# doan1.net
KiCad netlist of a schematic drawn in Altium Designer
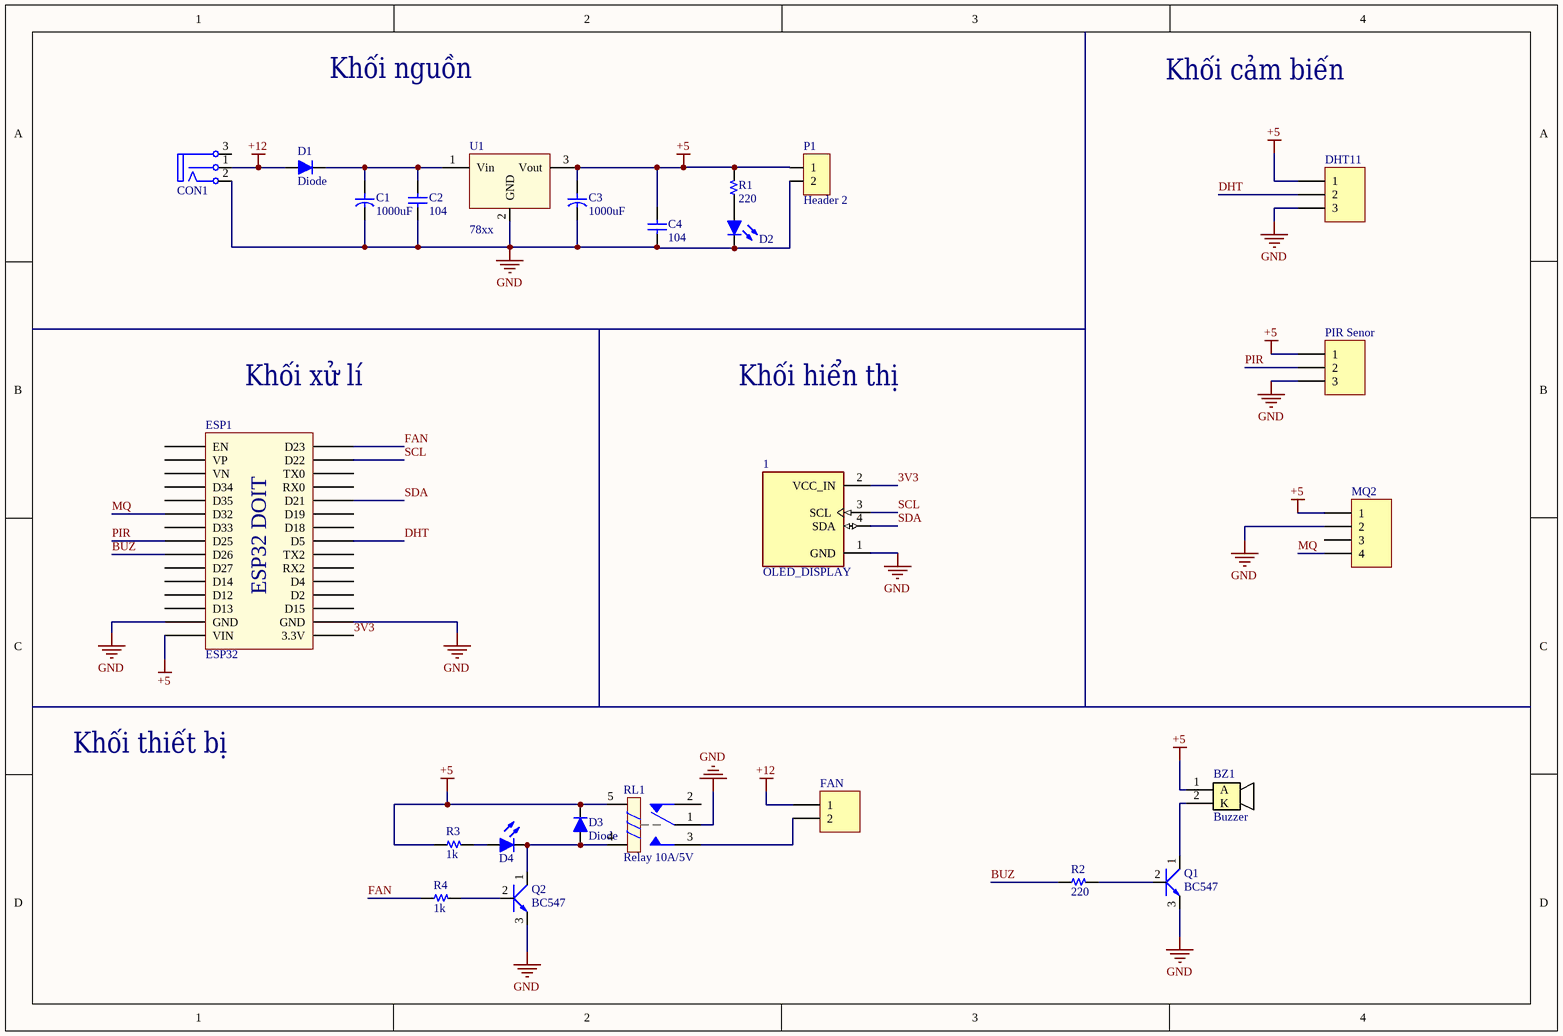
[diagram p0: doan1.SchDoc]

(export (version "E")
  (design (tool "Eeschema 10.0.6"))
  (components
    (comp (ref "1")
      (value "OLED_DISPLAY")
      (footprint "MODULE_DM-OLED096-636")
      (description "0.96â€ 128 X 64 MONOCHROME GRAPHIC OLED DISPLAY MODULE - I2C")
      (fields (field (name "MF") "Display Module") (field (name "MP") "DM-OLED096-636"))
      (libsource (lib "DM-OLED096-636") (part "DM-OLED096-636"))
    )
    (comp (ref "BZ1") (value "Buzzer") (footprint "BUZZER") (libsource (lib "chipfc_libs") (part "Buzzer")))
    (comp (ref "C1")
      (value "1000uF")
      (footprint "CYL/D.400/LS.200")
      (description "Capacitor pol")
      (libsource (lib "chipfc_libs") (part "Capacitor"))
    )
    (comp (ref "C2")
      (value "104")
      (footprint "CAP Ceramic/W300")
      (description "Capacitor non-pol")
      (libsource (lib "chipfc_libs") (part "Capacitor NP"))
    )
    (comp (ref "C3")
      (value "1000uF")
      (footprint "CYL/D.400/LS.200")
      (description "Capacitor pol")
      (libsource (lib "chipfc_libs") (part "Capacitor"))
    )
    (comp (ref "C4")
      (value "104")
      (footprint "CAP Ceramic/W300")
      (description "Capacitor non-pol")
      (libsource (lib "chipfc_libs") (part "Capacitor NP"))
    )
    (comp (ref "CON1")
      (value "CON DC PWR")
      (footprint "CONN/DC/PWR/5.0MM")
      (description "DC input connector")
      (libsource (lib "connectors") (part "CON DC PWR"))
    )
    (comp (ref "D1")
      (value "Diode")
      (footprint "DO-41")
      (description "Default Diode")
      (libsource (lib "chipfc_libs") (part "Diode"))
    )
    (comp (ref "D2")
      (value "Led")
      (footprint "LED 3MM - red")
      (description "Typical LED")
      (libsource (lib "led") (part "Led"))
    )
    (comp (ref "D3")
      (value "Diode")
      (footprint "DO-41")
      (description "Default Diode")
      (libsource (lib "chipfc_libs") (part "Diode"))
    )
    (comp (ref "D4")
      (value "Led")
      (footprint "LED 3MM - red")
      (description "Typical LED")
      (libsource (lib "led") (part "Led"))
    )
    (comp (ref "DHT11")
      (value "Header 3")
      (footprint "MY_FE03")
      (description "Header, 3-Pin")
      (fields (field (name "ASID PART NUMBER") "Header 3-AS"))
      (libsource (lib "003 Mylib-Rev-4") (part "Header 3"))
    )
    (comp (ref "ESP1")
      (value "ESP32")
      (footprint "ESP32 WROOM 32 KIT")
      (libsource (lib "Altium_Lib_by_KhueNguyenCreator") (part "ESP32 WROOM 32 KIT"))
    )
    (comp (ref "FAN")
      (value "Header 2")
      (footprint "My_CN2")
      (description "Header, 2-Pin")
      (fields (field (name "ASID PART NUMBER") "Header 2-AS"))
      (libsource (lib "003 Mylib-Rev-4") (part "Header 2"))
    )
    (comp (ref "MQ2")
      (value "Header 4")
      (footprint "MY_FE04")
      (description "Header, 4-Pin")
      (fields (field (name "ASID PART NUMBER") "Header 4-AS"))
      (libsource (lib "003 Mylib-Rev-4") (part "Header 4"))
    )
    (comp (ref "P1")
      (value "Header 2")
      (footprint "HDR/Header/2")
      (description "Header, 2-Pin")
      (libsource (lib "connectors") (part "Header 2"))
    )
    (comp (ref "PIR Senor")
      (value "Header 3")
      (footprint "MY_FE03W")
      (description "Header, 3-Pin")
      (fields (field (name "ASID PART NUMBER") "Header 3-AS"))
      (libsource (lib "003 Mylib-Rev-4") (part "Header 3"))
    )
    (comp (ref "Q1")
      (value "BC547")
      (footprint "QTO-92")
      (description "NPN 600mW, ECB")
      (libsource (lib "syhaunguyen") (part "C1815"))
    )
    (comp (ref "Q2")
      (value "BC547")
      (footprint "QTO-92")
      (description "NPN 600mW, ECB")
      (libsource (lib "syhaunguyen") (part "C1815"))
    )
    (comp (ref "R1")
      (value "220")
      (footprint "R 1/4W/300")
      (description "Resistor")
      (libsource (lib "chipfc_libs") (part "Resistor"))
    )
    (comp (ref "R2")
      (value "220")
      (footprint "R 1/4W/300")
      (description "Resistor")
      (libsource (lib "chipfc_libs") (part "Resistor"))
    )
    (comp (ref "R3")
      (value "1k")
      (footprint "R 1/4W/300")
      (description "Resistor")
      (libsource (lib "chipfc_libs") (part "Resistor"))
    )
    (comp (ref "R4")
      (value "1k")
      (footprint "R 1/4W/300")
      (description "Resistor")
      (libsource (lib "chipfc_libs") (part "Resistor"))
    )
    (comp (ref "RL1")
      (value "Relay 10A/5V")
      (footprint "RL_SPDT_10A")
      (description "Relay SPDT,10A - 12VDC 5 Pin")
      (libsource (lib "syhaunguyen") (part "Relay 1"))
    )
    (comp (ref "U1")
      (value "78xx")
      (footprint "TO-220")
      (description "LDO Fixed Voltage regulator")
      (libsource (lib "chipfc_libs") (part "78xx"))
    )
  )
  (nets
    (net (code "1") (name "+5") (class "Default")
      (node (ref "BZ1") (pin "1") (pinfunction "A_1") (pintype "passive"))
      (node (ref "C3") (pin "1") (pinfunction "1_1") (pintype "passive"))
      (node (ref "C4") (pin "1") (pinfunction "1_1") (pintype "passive"))
      (node (ref "D3") (pin "2") (pinfunction "K_2") (pintype "passive"))
      (node (ref "DHT11") (pin "1") (pinfunction "1_1") (pintype "passive"))
      (node (ref "ESP1") (pin "15") (pinfunction "VIN_15") (pintype "passive"))
      (node (ref "MQ2") (pin "1") (pinfunction "1_1") (pintype "passive"))
      (node (ref "P1") (pin "1") (pinfunction "1_1") (pintype "passive"))
      (node (ref "PIR Senor") (pin "1") (pinfunction "1_1") (pintype "passive"))
      (node (ref "R1") (pin "2") (pinfunction "2_2") (pintype "passive"))
      (node (ref "R3") (pin "1") (pinfunction "1_1") (pintype "passive"))
      (node (ref "RL1") (pin "5") (pinfunction "5_5") (pintype "passive"))
      (node (ref "U1") (pin "3") (pinfunction "Vout_3") (pintype "passive"))
    )
    (net (code "2") (name "+12") (class "Default")
      (node (ref "CON1") (pin "1") (pinfunction "S_1") (pintype "power_in"))
      (node (ref "D1") (pin "1") (pinfunction "A_1") (pintype "passive"))
      (node (ref "FAN") (pin "1") (pinfunction "1_1") (pintype "passive"))
    )
    (net (code "3") (name "/3V3") (class "Default")
      (node (ref "1") (pin "2") (pinfunction "VCC_IN_2") (pintype "power_in"))
      (node (ref "ESP1") (pin "16") (pinfunction "3.3V_16") (pintype "passive"))
    )
    (net (code "4") (name "/BUZ") (class "Default")
      (node (ref "ESP1") (pin "9") (pinfunction "D26_9") (pintype "passive"))
      (node (ref "R2") (pin "1") (pinfunction "1_1") (pintype "passive"))
    )
    (net (code "5") (name "/DHT") (class "Default")
      (node (ref "DHT11") (pin "2") (pinfunction "2_2") (pintype "passive"))
      (node (ref "ESP1") (pin "23") (pinfunction "D5_23") (pintype "passive"))
    )
    (net (code "6") (name "/FAN") (class "Default")
      (node (ref "ESP1") (pin "30") (pinfunction "D23_30") (pintype "passive"))
      (node (ref "R4") (pin "1") (pinfunction "1_1") (pintype "passive"))
    )
    (net (code "7") (name "/MQ") (class "Default")
      (node (ref "ESP1") (pin "6") (pinfunction "D32_6") (pintype "passive"))
      (node (ref "MQ2") (pin "4") (pinfunction "4_4") (pintype "passive"))
    )
    (net (code "8") (name "/PIR") (class "Default")
      (node (ref "ESP1") (pin "8") (pinfunction "D25_8") (pintype "passive"))
      (node (ref "PIR Senor") (pin "2") (pinfunction "2_2") (pintype "passive"))
    )
    (net (code "9") (name "/SCL") (class "Default")
      (node (ref "1") (pin "3") (pinfunction "SCL_3") (pintype "input"))
      (node (ref "ESP1") (pin "29") (pinfunction "D22_29") (pintype "passive"))
    )
    (net (code "10") (name "/SDA") (class "Default")
      (node (ref "1") (pin "4") (pinfunction "SDA_4") (pintype "bidirectional"))
      (node (ref "ESP1") (pin "26") (pinfunction "D21_26") (pintype "passive"))
    )
    (net (code "11") (name "GND") (class "Default")
      (node (ref "1") (pin "1") (pinfunction "GND_1") (pintype "power_in"))
      (node (ref "C1") (pin "2") (pinfunction "2_2") (pintype "passive"))
      (node (ref "C2") (pin "2") (pinfunction "2_2") (pintype "passive"))
      (node (ref "C3") (pin "2") (pinfunction "2_2") (pintype "passive"))
      (node (ref "C4") (pin "2") (pinfunction "2_2") (pintype "passive"))
      (node (ref "CON1") (pin "2") (pinfunction "T_2") (pintype "passive"))
      (node (ref "D2") (pin "2") (pinfunction "K_2") (pintype "passive"))
      (node (ref "DHT11") (pin "3") (pinfunction "3_3") (pintype "passive"))
      (node (ref "ESP1") (pin "14") (pinfunction "GND_14") (pintype "passive"))
      (node (ref "ESP1") (pin "17") (pinfunction "GND_17") (pintype "passive"))
      (node (ref "MQ2") (pin "2") (pinfunction "2_2") (pintype "passive"))
      (node (ref "P1") (pin "2") (pinfunction "2_2") (pintype "passive"))
      (node (ref "PIR Senor") (pin "3") (pinfunction "3_3") (pintype "passive"))
      (node (ref "Q1") (pin "3") (pinfunction "C_3") (pintype "passive"))
      (node (ref "Q2") (pin "3") (pinfunction "C_3") (pintype "passive"))
      (node (ref "RL1") (pin "1") (pinfunction "1_1") (pintype "passive"))
      (node (ref "U1") (pin "2") (pinfunction "GND_2") (pintype "passive"))
    )
    (net (code "12") (name "Net-(BZ1-K)") (class "Default")
      (node (ref "BZ1") (pin "2") (pinfunction "K_2") (pintype "passive"))
      (node (ref "Q1") (pin "1") (pinfunction "B_1") (pintype "passive"))
    )
    (net (code "13") (name "Net-(D1-K)") (class "Default")
      (node (ref "C1") (pin "1") (pinfunction "1_1") (pintype "passive"))
      (node (ref "C2") (pin "1") (pinfunction "1_1") (pintype "passive"))
      (node (ref "D1") (pin "2") (pinfunction "K_2") (pintype "passive"))
      (node (ref "U1") (pin "1") (pinfunction "Vin_1") (pintype "power_in"))
    )
    (net (code "14") (name "Net-(D2-A)") (class "Default")
      (node (ref "D2") (pin "1") (pinfunction "A_1") (pintype "passive"))
      (node (ref "R1") (pin "1") (pinfunction "1_1") (pintype "passive"))
    )
    (net (code "15") (name "Net-(D3-A)") (class "Default")
      (node (ref "D3") (pin "1") (pinfunction "A_1") (pintype "passive"))
      (node (ref "D4") (pin "2") (pinfunction "K_2") (pintype "passive"))
      (node (ref "Q2") (pin "1") (pinfunction "B_1") (pintype "passive"))
      (node (ref "RL1") (pin "4") (pinfunction "4_4") (pintype "passive"))
    )
    (net (code "16") (name "Net-(D4-A)") (class "Default")
      (node (ref "D4") (pin "1") (pinfunction "A_1") (pintype "passive"))
      (node (ref "R3") (pin "2") (pinfunction "2_2") (pintype "passive"))
    )
    (net (code "17") (name "Net-(FAN-Pad2)") (class "Default")
      (node (ref "FAN") (pin "2") (pinfunction "2_2") (pintype "passive"))
      (node (ref "RL1") (pin "3") (pinfunction "3_3") (pintype "passive"))
    )
    (net (code "18") (name "Net-(Q1-E)") (class "Default")
      (node (ref "Q1") (pin "2") (pinfunction "E_2") (pintype "passive"))
      (node (ref "R2") (pin "2") (pinfunction "2_2") (pintype "passive"))
    )
    (net (code "19") (name "Net-(Q2-E)") (class "Default")
      (node (ref "Q2") (pin "2") (pinfunction "E_2") (pintype "passive"))
      (node (ref "R4") (pin "2") (pinfunction "2_2") (pintype "passive"))
    )
    (net (code "20") (name "unconnected-(CON1-TN-Pad3)") (class "Default")
      (node (ref "CON1") (pin "3") (pinfunction "TN_3") (pintype "passive"))
    )
    (net (code "21") (name "unconnected-(ESP1-D2-Pad19)") (class "Default")
      (node (ref "ESP1") (pin "19") (pinfunction "D2_19") (pintype "passive"))
    )
    (net (code "22") (name "unconnected-(ESP1-D4-Pad20)") (class "Default")
      (node (ref "ESP1") (pin "20") (pinfunction "D4_20") (pintype "passive"))
    )
    (net (code "23") (name "unconnected-(ESP1-D12-Pad12)") (class "Default")
      (node (ref "ESP1") (pin "12") (pinfunction "D12_12") (pintype "passive"))
    )
    (net (code "24") (name "unconnected-(ESP1-D13-Pad13)") (class "Default")
      (node (ref "ESP1") (pin "13") (pinfunction "D13_13") (pintype "passive"))
    )
    (net (code "25") (name "unconnected-(ESP1-D14-Pad11)") (class "Default")
      (node (ref "ESP1") (pin "11") (pinfunction "D14_11") (pintype "passive"))
    )
    (net (code "26") (name "unconnected-(ESP1-D15-Pad18)") (class "Default")
      (node (ref "ESP1") (pin "18") (pinfunction "D15_18") (pintype "passive"))
    )
    (net (code "27") (name "unconnected-(ESP1-D18-Pad24)") (class "Default")
      (node (ref "ESP1") (pin "24") (pinfunction "D18_24") (pintype "passive"))
    )
    (net (code "28") (name "unconnected-(ESP1-D19-Pad25)") (class "Default")
      (node (ref "ESP1") (pin "25") (pinfunction "D19_25") (pintype "passive"))
    )
    (net (code "29") (name "unconnected-(ESP1-D27-Pad10)") (class "Default")
      (node (ref "ESP1") (pin "10") (pinfunction "D27_10") (pintype "passive"))
    )
    (net (code "30") (name "unconnected-(ESP1-D33-Pad7)") (class "Default")
      (node (ref "ESP1") (pin "7") (pinfunction "D33_7") (pintype "passive"))
    )
    (net (code "31") (name "unconnected-(ESP1-D34-Pad4)") (class "Default")
      (node (ref "ESP1") (pin "4") (pinfunction "D34_4") (pintype "passive"))
    )
    (net (code "32") (name "unconnected-(ESP1-D35-Pad5)") (class "Default")
      (node (ref "ESP1") (pin "5") (pinfunction "D35_5") (pintype "passive"))
    )
    (net (code "33") (name "unconnected-(ESP1-EN-Pad1)") (class "Default")
      (node (ref "ESP1") (pin "1") (pinfunction "EN_1") (pintype "passive"))
    )
    (net (code "34") (name "unconnected-(ESP1-RX0-Pad27)") (class "Default")
      (node (ref "ESP1") (pin "27") (pinfunction "RX0_27") (pintype "passive"))
    )
    (net (code "35") (name "unconnected-(ESP1-RX2-Pad21)") (class "Default")
      (node (ref "ESP1") (pin "21") (pinfunction "RX2_21") (pintype "passive"))
    )
    (net (code "36") (name "unconnected-(ESP1-TX0-Pad28)") (class "Default")
      (node (ref "ESP1") (pin "28") (pinfunction "TX0_28") (pintype "passive"))
    )
    (net (code "37") (name "unconnected-(ESP1-TX2-Pad22)") (class "Default")
      (node (ref "ESP1") (pin "22") (pinfunction "TX2_22") (pintype "passive"))
    )
    (net (code "38") (name "unconnected-(ESP1-VN-Pad3)") (class "Default")
      (node (ref "ESP1") (pin "3") (pinfunction "VN_3") (pintype "passive"))
    )
    (net (code "39") (name "unconnected-(ESP1-VP-Pad2)") (class "Default")
      (node (ref "ESP1") (pin "2") (pinfunction "VP_2") (pintype "passive"))
    )
    (net (code "40") (name "unconnected-(MQ2-Pad3)") (class "Default")
      (node (ref "MQ2") (pin "3") (pinfunction "3_3") (pintype "passive"))
    )
    (net (code "41") (name "unconnected-(RL1-Pad2)") (class "Default")
      (node (ref "RL1") (pin "2") (pinfunction "2_2") (pintype "passive"))
    )
  )
)
